# Adjustable_DCDC.net
KiCad netlist of a schematic drawn in Altium Designer
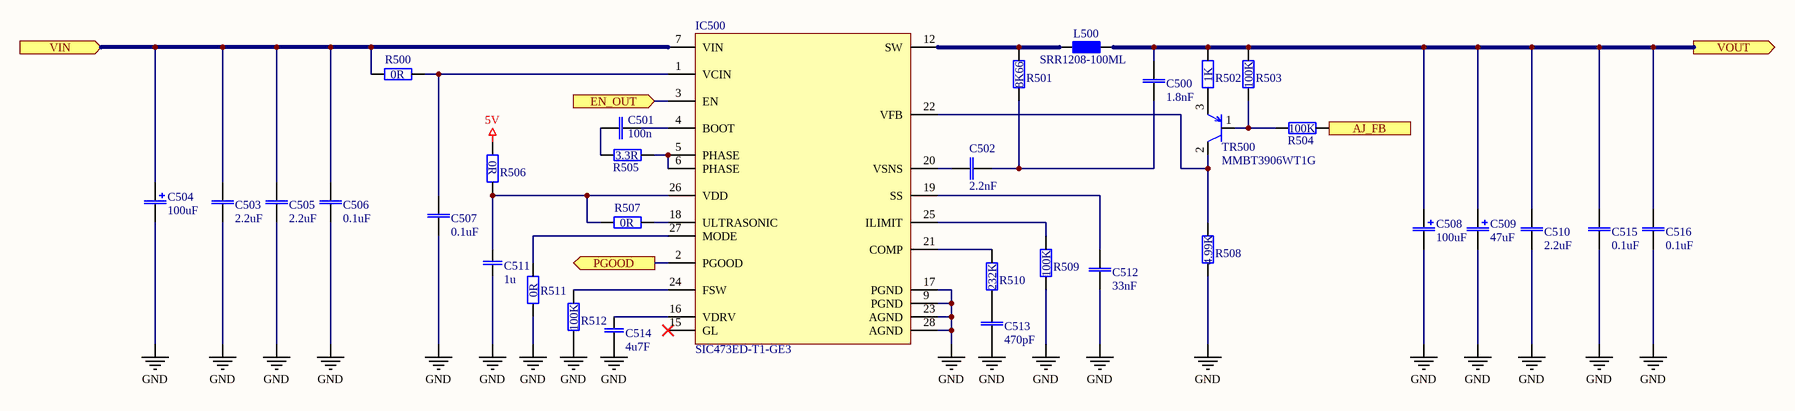
[diagram p0: Adjustable_DCDC.SchDoc]

(export (version "E")
  (design (tool "Eeschema 10.0.6"))
  (components
    (comp (ref "C500")
      (value "1.8nF")
      (footprint "CAP0402")
      (fields (field (name "MPN") "CC0402KPX7R9BB182"))
      (libsource (lib "Passive") (part "CC0402KPX7R9BB182"))
    )
    (comp (ref "C501")
      (value "100n")
      (footprint "CAP0402")
      (fields (field (name "MPN") "CL05A104KA5NNNC") (field (name "TOLERANCE") "10%"))
      (libsource (lib "Schematic") (part "CL05A104KA5NNNC"))
    )
    (comp (ref "C502")
      (value "2.2nF")
      (footprint "CAP0402")
      (fields (field (name "MPN") "CC0402KRX7R9BB222"))
      (libsource (lib "Passive") (part "CC0402KRX7R9BB222"))
    )
    (comp (ref "C503")
      (value "2.2uF")
      (footprint "CAP1206")
      (fields (field (name "MPN") "CL31B225KCHSNNE"))
      (libsource (lib "Passive") (part "CL31B225KCHSNNE"))
    )
    (comp (ref "C504")
      (value "100uF")
      (footprint "CHEMICON_D10H10_JA0")
      (fields (field (name "MPN") "EMVE630ARA101MJA0G"))
      (libsource (lib "Passive") (part "EMVE630ARA101MJA0G"))
    )
    (comp (ref "C505")
      (value "2.2uF")
      (footprint "CAP0805")
      (description "0805")
      (fields (field (name "MPN") "GRM21BD72A225ME01K"))
      (libsource (lib "Passive") (part "GRM21BD72A225ME01K"))
    )
    (comp (ref "C506")
      (value "0.1uF")
      (footprint "CAP0402")
      (description "0805")
      (fields (field (name "MPN") "GRM155R62A104KE14D"))
      (libsource (lib "Passive") (part "GRM155R62A104KE14D"))
    )
    (comp (ref "C507")
      (value "0.1uF")
      (footprint "CAP0402")
      (description "0805")
      (fields (field (name "MPN") "GRM155R62A104KE14D"))
      (libsource (lib "Passive") (part "GRM155R62A104KE14D"))
    )
    (comp (ref "C508")
      (value "100uF")
      (footprint "CHEMICON_D10H10_JA0")
      (fields (field (name "MPN") "EMVE630ARA101MJA0G"))
      (libsource (lib "Passive") (part "EMVE630ARA101MJA0G"))
    )
    (comp (ref "C509")
      (value "47uF")
      (footprint "CHEMICON_KOND_D8H10")
      (fields (field (name "MPN") "HHXC500ARA470MHA0G"))
      (libsource (lib "Passive") (part "HHXC500ARA470MHA0G"))
    )
    (comp (ref "C510")
      (value "2.2uF")
      (footprint "CAP1206")
      (fields (field (name "MPN") "CL31B225KCHSNNE"))
      (libsource (lib "Passive") (part "CL31B225KCHSNNE"))
    )
    (comp (ref "C511")
      (value "1u")
      (footprint "0603")
      (fields (field (name "PART NUMBER") "000088"))
      (libsource (lib "TychosLibrary") (part "Capacitor"))
    )
    (comp (ref "C512")
      (value "33nF")
      (footprint "CAP0402")
      (fields (field (name "MPN") "C0402C333K4RECTU"))
      (libsource (lib "Passive") (part "C0402C333K4RECTU"))
    )
    (comp (ref "C513")
      (value "470pF")
      (footprint "CAP0402")
      (fields (field (name "MPN") "CL05B471KB5NNNC"))
      (libsource (lib "Passive") (part "CL05B471KB5NNNC"))
    )
    (comp (ref "C514")
      (value "4u7F")
      (footprint "0805")
      (fields (field (name "PART NUMBER") "000090") (field (name "MPN") "CL21A475KOFNNNE"))
      (libsource (lib "TychosLibrary") (part "Capacitor"))
    )
    (comp (ref "C515")
      (value "0.1uF")
      (footprint "CAP0402")
      (description "0805")
      (fields (field (name "MPN") "GRM155R62A104KE14D"))
      (libsource (lib "Passive") (part "GRM155R62A104KE14D"))
    )
    (comp (ref "C516")
      (value "0.1uF")
      (footprint "CAP0402")
      (description "0805")
      (fields (field (name "MPN") "GRM155R62A104KE14D"))
      (libsource (lib "Passive") (part "GRM155R62A104KE14D"))
    )
    (comp (ref "IC500")
      (value "SIC473ED-T1-GE3")
      (footprint "VISCHAY_SiC47X")
      (libsource (lib "Schematic") (part "SIC473ED-T1-GE3"))
    )
    (comp (ref "L500")
      (value "SRR1208-100ML")
      (footprint "SRR1208")
      (libsource (lib "Passive") (part "SRR1208-100ML"))
    )
    (comp (ref "R500")
      (value "0R")
      (footprint "RES0402")
      (fields (field (name "MPN") "RC0402JR-070RL"))
      (libsource (lib "Passive") (part "RES_0402"))
    )
    (comp (ref "R501")
      (value "RC0402FR-078K66L")
      (footprint "RES0402")
      (libsource (lib "Passive") (part "RC0402FR-078K66L"))
    )
    (comp (ref "R502")
      (value "RC0402FR-071KL")
      (footprint "RES0402")
      (libsource (lib "Schematic") (part "RC0402FR-071KL"))
    )
    (comp (ref "R503")
      (value "RC0402FR-07100KL")
      (footprint "RES0402")
      (libsource (lib "Schematic") (part "RC0402FR-07100KL"))
    )
    (comp (ref "R504")
      (value "RC0402FR-07100KL")
      (footprint "RES0402")
      (libsource (lib "Schematic") (part "RC0402FR-07100KL"))
    )
    (comp (ref "R505")
      (value "RC0402FR-073R3L")
      (footprint "RES0402")
      (libsource (lib "Passive") (part "RC0402FR-073R3L"))
    )
    (comp (ref "R506")
      (value "0R")
      (footprint "RES0402")
      (fields (field (name "MPN") "RC0402JR-070RL"))
      (libsource (lib "Passive") (part "RES_0402"))
    )
    (comp (ref "R507")
      (value "0R")
      (footprint "RES0402")
      (fields (field (name "MPN") "RC0402JR-070RL"))
      (libsource (lib "Passive") (part "RES_0402"))
    )
    (comp (ref "R508")
      (value "RC0402FR-074K99L")
      (footprint "RES0402")
      (libsource (lib "Schematic") (part "RC0402FR-074K99L"))
    )
    (comp (ref "R509")
      (value "RC0402FR-07100KL")
      (footprint "RES0402")
      (libsource (lib "Schematic") (part "RC0402FR-07100KL"))
    )
    (comp (ref "R510")
      (value "RC0402FR-07232KL")
      (footprint "RES0402")
      (libsource (lib "Passive") (part "RC0402FR-07232KL"))
    )
    (comp (ref "R511")
      (value "0R")
      (footprint "RES0402")
      (fields (field (name "MPN") "RC0402JR-070RL"))
      (libsource (lib "Passive") (part "RES_0402"))
    )
    (comp (ref "R512")
      (value "RC0402FR-07100KL")
      (footprint "RES0402")
      (libsource (lib "Schematic") (part "RC0402FR-07100KL"))
    )
    (comp (ref "TR500")
      (value "MMBT3906WT1G")
      (footprint "SOT323/SC-70(NX6008NBKW)")
      (libsource (lib "Schematic") (part "MMBT3906WT1G"))
    )
  )
  (nets
    (net (code "1") (name "/AJ_FB") (class "Default")
      (node (ref "R504") (pin "2") (pinfunction "2_2") (pintype "passive"))
    )
    (net (code "2") (name "/EN_OUT") (class "Default")
      (node (ref "IC500") (pin "3") (pinfunction "EN_3") (pintype "passive"))
    )
    (net (code "3") (name "/PGOOD") (class "Default")
      (node (ref "IC500") (pin "2") (pinfunction "PGOOD_2") (pintype "passive"))
    )
    (net (code "4") (name "/VIN") (class "Default")
      (node (ref "C503") (pin "2") (pinfunction "2_2") (pintype "passive"))
      (node (ref "C504") (pin "1") (pinfunction "1_1") (pintype "passive"))
      (node (ref "C505") (pin "2") (pinfunction "2_2") (pintype "passive"))
      (node (ref "C506") (pin "2") (pinfunction "2_2") (pintype "passive"))
      (node (ref "IC500") (pin "7") (pinfunction "VIN_7") (pintype "passive"))
      (node (ref "R500") (pin "1") (pinfunction "1_1") (pintype "passive"))
    )
    (net (code "5") (name "/VOUT") (class "Default")
      (node (ref "C500") (pin "2") (pinfunction "2_2") (pintype "passive"))
      (node (ref "C508") (pin "1") (pinfunction "1_1") (pintype "passive"))
      (node (ref "C509") (pin "1") (pinfunction "1_1") (pintype "passive"))
      (node (ref "C510") (pin "2") (pinfunction "2_2") (pintype "passive"))
      (node (ref "C515") (pin "2") (pinfunction "2_2") (pintype "passive"))
      (node (ref "C516") (pin "2") (pinfunction "2_2") (pintype "passive"))
      (node (ref "L500") (pin "2") (pinfunction "2_2") (pintype "passive"))
      (node (ref "R502") (pin "2") (pinfunction "2_2") (pintype "passive"))
      (node (ref "R503") (pin "2") (pinfunction "2_2") (pintype "passive"))
    )
    (net (code "6") (name "5V") (class "Default")
      (node (ref "R506") (pin "1") (pinfunction "1_1") (pintype "passive"))
    )
    (net (code "7") (name "GND") (class "Default")
      (node (ref "C503") (pin "1") (pinfunction "1_1") (pintype "passive"))
      (node (ref "C504") (pin "2") (pinfunction "2_2") (pintype "passive"))
      (node (ref "C505") (pin "1") (pinfunction "1_1") (pintype "passive"))
      (node (ref "C506") (pin "1") (pinfunction "1_1") (pintype "passive"))
      (node (ref "C507") (pin "1") (pinfunction "1_1") (pintype "passive"))
      (node (ref "C508") (pin "2") (pinfunction "2_2") (pintype "passive"))
      (node (ref "C509") (pin "2") (pinfunction "2_2") (pintype "passive"))
      (node (ref "C510") (pin "1") (pinfunction "1_1") (pintype "passive"))
      (node (ref "C511") (pin "1") (pinfunction "1_1") (pintype "passive"))
      (node (ref "C512") (pin "1") (pinfunction "1_1") (pintype "passive"))
      (node (ref "C513") (pin "1") (pinfunction "1_1") (pintype "passive"))
      (node (ref "C514") (pin "1") (pinfunction "1_1") (pintype "passive"))
      (node (ref "C515") (pin "1") (pinfunction "1_1") (pintype "passive"))
      (node (ref "C516") (pin "1") (pinfunction "1_1") (pintype "passive"))
      (node (ref "IC500") (pin "17") (pinfunction "PGND_17") (pintype "passive"))
      (node (ref "IC500") (pin "23") (pinfunction "AGND_23") (pintype "passive"))
      (node (ref "IC500") (pin "28") (pinfunction "AGND_28") (pintype "passive"))
      (node (ref "IC500") (pin "9") (pinfunction "PGND_9") (pintype "passive"))
      (node (ref "R508") (pin "1") (pinfunction "1_1") (pintype "passive"))
      (node (ref "R509") (pin "1") (pinfunction "1_1") (pintype "passive"))
      (node (ref "R511") (pin "1") (pinfunction "1_1") (pintype "passive"))
      (node (ref "R512") (pin "1") (pinfunction "1_1") (pintype "passive"))
    )
    (net (code "8") (name "Net-(C500-Pad1)") (class "Default")
      (node (ref "C500") (pin "1") (pinfunction "1_1") (pintype "passive"))
      (node (ref "C502") (pin "2") (pinfunction "2_2") (pintype "passive"))
      (node (ref "R501") (pin "1") (pinfunction "1_1") (pintype "passive"))
    )
    (net (code "9") (name "Net-(C501-Pad2)") (class "Default")
      (node (ref "C501") (pin "2") (pinfunction "2_2") (pintype "passive"))
      (node (ref "R505") (pin "1") (pinfunction "1_1") (pintype "passive"))
    )
    (net (code "10") (name "Net-(C513-Pad2)") (class "Default")
      (node (ref "C513") (pin "2") (pinfunction "2_2") (pintype "passive"))
      (node (ref "R510") (pin "1") (pinfunction "1_1") (pintype "passive"))
    )
    (net (code "11") (name "Net-(IC500-BOOT)") (class "Default")
      (node (ref "C501") (pin "1") (pinfunction "1_1") (pintype "passive"))
      (node (ref "IC500") (pin "4") (pinfunction "BOOT_4") (pintype "passive"))
    )
    (net (code "12") (name "Net-(IC500-COMP)") (class "Default")
      (node (ref "IC500") (pin "21") (pinfunction "COMP_21") (pintype "passive"))
      (node (ref "R510") (pin "2") (pinfunction "2_2") (pintype "passive"))
    )
    (net (code "13") (name "Net-(IC500-FSW)") (class "Default")
      (node (ref "IC500") (pin "24") (pinfunction "FSW_24") (pintype "passive"))
      (node (ref "R512") (pin "2") (pinfunction "2_2") (pintype "passive"))
    )
    (net (code "14") (name "Net-(IC500-ILIMIT)") (class "Default")
      (node (ref "IC500") (pin "25") (pinfunction "ILIMIT_25") (pintype "passive"))
      (node (ref "R509") (pin "2") (pinfunction "2_2") (pintype "passive"))
    )
    (net (code "15") (name "Net-(IC500-MODE)") (class "Default")
      (node (ref "IC500") (pin "27") (pinfunction "MODE_27") (pintype "passive"))
      (node (ref "R511") (pin "2") (pinfunction "2_2") (pintype "passive"))
    )
    (net (code "16") (name "Net-(IC500-PHASE-Pad5)") (class "Default")
      (node (ref "IC500") (pin "5") (pinfunction "PHASE_5") (pintype "passive"))
      (node (ref "IC500") (pin "6") (pinfunction "PHASE_6") (pintype "passive"))
      (node (ref "R505") (pin "2") (pinfunction "2_2") (pintype "passive"))
    )
    (net (code "17") (name "Net-(IC500-SS)") (class "Default")
      (node (ref "C512") (pin "2") (pinfunction "2_2") (pintype "passive"))
      (node (ref "IC500") (pin "19") (pinfunction "SS_19") (pintype "passive"))
    )
    (net (code "18") (name "Net-(IC500-SW)") (class "Default")
      (node (ref "IC500") (pin "12") (pinfunction "SW_12") (pintype "passive"))
      (node (ref "L500") (pin "1") (pinfunction "1_1") (pintype "passive"))
      (node (ref "R501") (pin "2") (pinfunction "2_2") (pintype "passive"))
    )
    (net (code "19") (name "Net-(IC500-ULTRASONIC)") (class "Default")
      (node (ref "IC500") (pin "18") (pinfunction "ULTRASONIC_18") (pintype "passive"))
      (node (ref "R507") (pin "2") (pinfunction "2_2") (pintype "passive"))
    )
    (net (code "20") (name "Net-(IC500-VCIN)") (class "Default")
      (node (ref "C507") (pin "2") (pinfunction "2_2") (pintype "passive"))
      (node (ref "IC500") (pin "1") (pinfunction "VCIN_1") (pintype "passive"))
      (node (ref "R500") (pin "2") (pinfunction "2_2") (pintype "passive"))
    )
    (net (code "21") (name "Net-(IC500-VDD)") (class "Default")
      (node (ref "C511") (pin "2") (pinfunction "2_2") (pintype "passive"))
      (node (ref "IC500") (pin "26") (pinfunction "VDD_26") (pintype "passive"))
      (node (ref "R506") (pin "2") (pinfunction "2_2") (pintype "passive"))
      (node (ref "R507") (pin "1") (pinfunction "1_1") (pintype "passive"))
    )
    (net (code "22") (name "Net-(IC500-VDRV)") (class "Default")
      (node (ref "C514") (pin "2") (pinfunction "2_2") (pintype "passive"))
      (node (ref "IC500") (pin "16") (pinfunction "VDRV_16") (pintype "passive"))
    )
    (net (code "23") (name "Net-(IC500-VFB)") (class "Default")
      (node (ref "IC500") (pin "22") (pinfunction "VFB_22") (pintype "passive"))
      (node (ref "R508") (pin "2") (pinfunction "2_2") (pintype "passive"))
      (node (ref "TR500") (pin "2") (pinfunction "E_2") (pintype "passive"))
    )
    (net (code "24") (name "Net-(IC500-VSNS)") (class "Default")
      (node (ref "C502") (pin "1") (pinfunction "1_1") (pintype "passive"))
      (node (ref "IC500") (pin "20") (pinfunction "VSNS_20") (pintype "passive"))
    )
    (net (code "25") (name "Net-(TR500-B)") (class "Default")
      (node (ref "R503") (pin "1") (pinfunction "1_1") (pintype "passive"))
      (node (ref "R504") (pin "1") (pinfunction "1_1") (pintype "passive"))
      (node (ref "TR500") (pin "1") (pinfunction "B_1") (pintype "passive"))
    )
    (net (code "26") (name "Net-(TR500-C)") (class "Default")
      (node (ref "R502") (pin "1") (pinfunction "1_1") (pintype "passive"))
      (node (ref "TR500") (pin "3") (pinfunction "C_3") (pintype "passive"))
    )
    (net (code "27") (name "unconnected-(IC500-GL-Pad15)") (class "Default")
      (node (ref "IC500") (pin "15") (pinfunction "GL_15") (pintype "passive+no_connect"))
    )
  )
)
